# STM32F103.net
KiCad netlist of a schematic drawn in Altium Designer
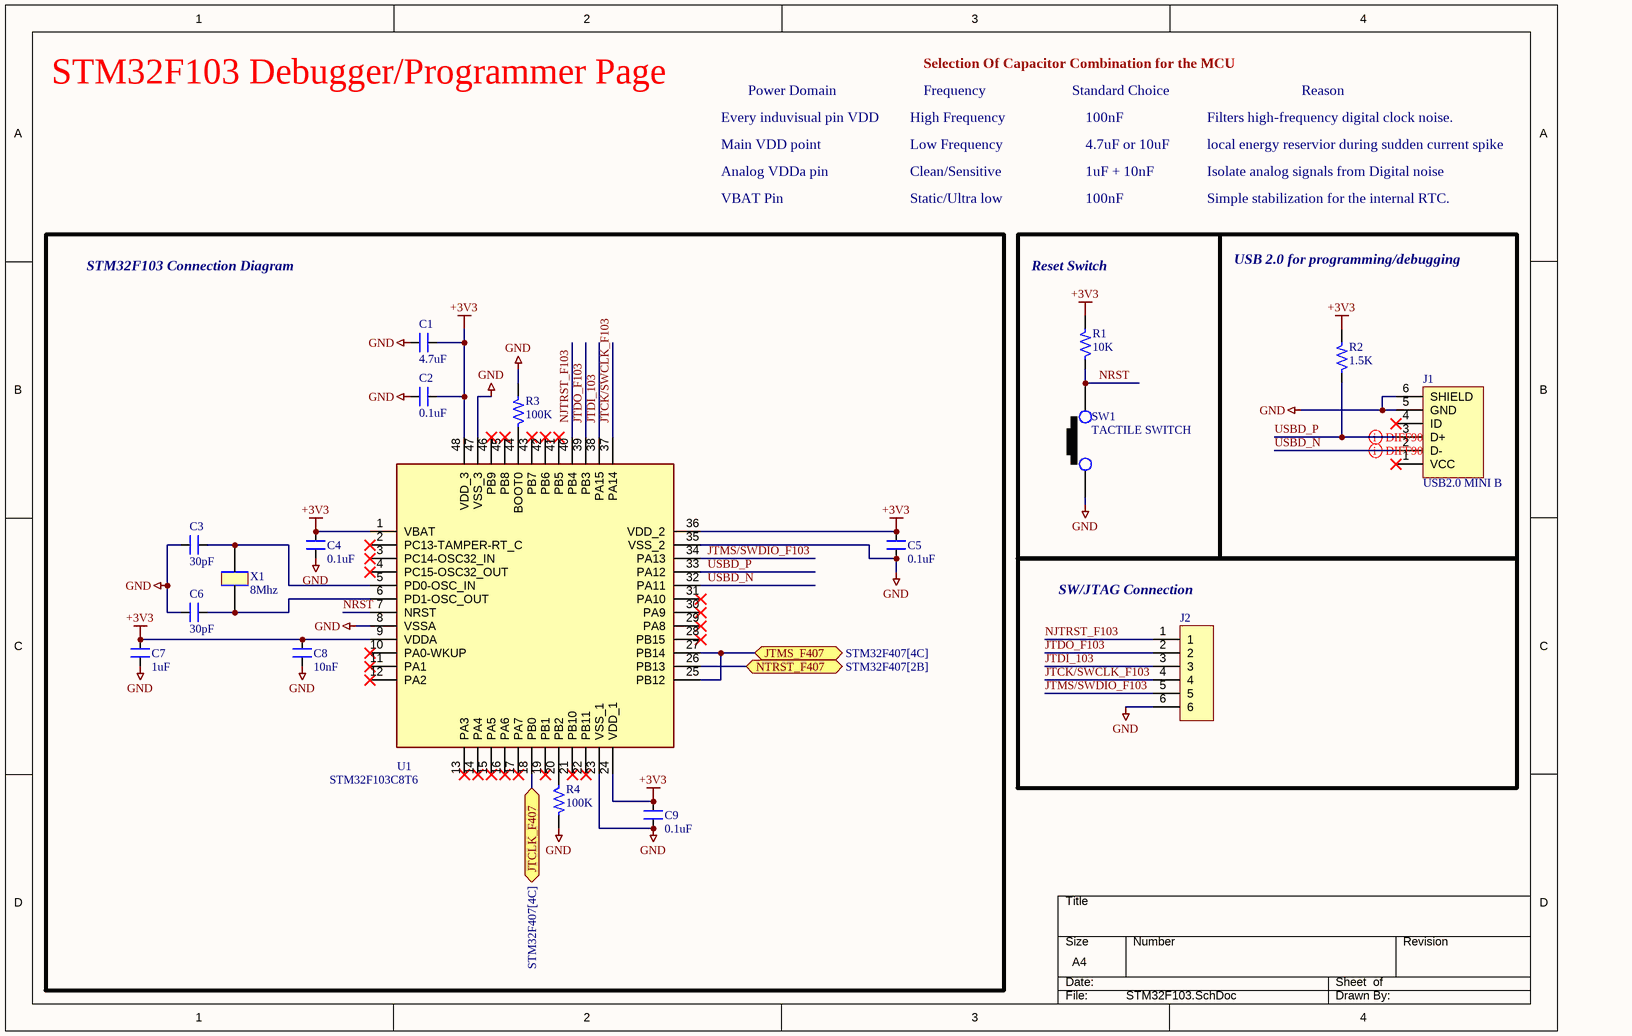
[diagram p0: STM32F103.SchDoc]

(export (version "E")
  (design (tool "Eeschema 10.0.6"))
  (components
    (comp (ref "C1")
      (value "4.7uF")
      (footprint "CAP_0805")
      (description "4.7µF ±10% 50V Ceramic Capacitor X5R 0805 (2012 Metric)")
      (fields
        (field (name "MANUFACTURER") "Yageo")
        (field (name "MANUFACTURER PART NUMBER") "GRM21BR61H475KE51L")
      )
      (libsource (lib "ESTEEMPCBLIB") (part "CAP_4.7uF-50V-10%-0805"))
    )
    (comp (ref "C2")
      (value "0.1uF")
      (footprint "CAP_0805")
      (description "0.1µF ±10% 50V Ceramic Capacitor X7R 0805 (2012 Metric)")
      (fields
        (field (name "MANUFACTURER") "Samsung")
        (field (name "MANUFACTURER PART NUMBER") "CL21B104KBCNNNC")
      )
      (libsource (lib "ESTEEMPCBLIB") (part "CAP_0.1uF-50V-10%-0805"))
    )
    (comp (ref "C3")
      (value "30pF")
      (footprint "CAP_0805")
      (description "±10% 50V Ceramic Capacitor C0G, NP0 0805 (2012 Metric)")
      (fields
        (field (name "MANUFACTURER PART NUMBER") "C0805C300K5GAC7800")
        (field (name "MANUFACTURER") "KEMET")
      )
      (libsource (lib "ESTEEMPCBLIB") (part "CAP_30pF-50V-10%-0805"))
    )
    (comp (ref "C4")
      (value "0.1uF")
      (footprint "CAP_0805")
      (description "0.1µF ±10% 50V Ceramic Capacitor X7R 0805 (2012 Metric)")
      (fields
        (field (name "MANUFACTURER") "Samsung")
        (field (name "MANUFACTURER PART NUMBER") "CL21B104KBCNNNC")
      )
      (libsource (lib "ESTEEMPCBLIB") (part "CAP_0.1uF-50V-10%-0805"))
    )
    (comp (ref "C5")
      (value "0.1uF")
      (footprint "CAP_0805")
      (description "0.1µF ±10% 50V Ceramic Capacitor X7R 0805 (2012 Metric)")
      (fields
        (field (name "MANUFACTURER") "Samsung")
        (field (name "MANUFACTURER PART NUMBER") "CL21B104KBCNNNC")
      )
      (libsource (lib "ESTEEMPCBLIB") (part "CAP_0.1uF-50V-10%-0805"))
    )
    (comp (ref "C6")
      (value "30pF")
      (footprint "CAP_0805")
      (description "±10% 50V Ceramic Capacitor C0G, NP0 0805 (2012 Metric)")
      (fields
        (field (name "MANUFACTURER PART NUMBER") "C0805C300K5GAC7800")
        (field (name "MANUFACTURER") "KEMET")
      )
      (libsource (lib "ESTEEMPCBLIB") (part "CAP_30pF-50V-10%-0805"))
    )
    (comp (ref "C7")
      (value "1uF")
      (footprint "CAP_0805")
      (description "1µF ±5% 50V Ceramic Capacitor X7R 0805 (2012 Metric)")
      (fields
        (field (name "MANUFACTURER") "Samsung")
        (field (name "MANUFACTURER PART NUMBER") "CC0805JKX7R9BB105")
      )
      (libsource (lib "ESTEEMPCBLIB") (part "CAP_1uF-50V-5%-0805"))
    )
    (comp (ref "C8")
      (value "10nF")
      (footprint "CAP_0805")
      (description "10000pF ±10% 50V Ceramic Capacitor X7R 0805 (2012 Metric)")
      (fields
        (field (name "MANUFACTURER") "Samsung")
        (field (name "MANUFACTURER PART NUMBER") "C0805C103K5RECAUTO")
      )
      (libsource (lib "ESTEEMPCBLIB") (part "CAP_10nF-50V-10%-0805"))
    )
    (comp (ref "C9")
      (value "0.1uF")
      (footprint "CAP_0805")
      (description "0.1µF ±10% 50V Ceramic Capacitor X7R 0805 (2012 Metric)")
      (fields
        (field (name "MANUFACTURER") "Samsung")
        (field (name "MANUFACTURER PART NUMBER") "CL21B104KBCNNNC")
      )
      (libsource (lib "ESTEEMPCBLIB") (part "CAP_0.1uF-50V-10%-0805"))
    )
    (comp (ref "J1")
      (value "USB2.0 MINI B")
      (footprint "CON_690-005-299-043")
      (description "USB - mini B USB 2.0 Receptacle Connector 5 Position Surface Mount, Right Angle")
      (fields
        (field (name "MANUFACTURER") "EDAC")
        (field (name "MANUFACTURER PART NUMBER") "690-005-299-043")
      )
      (libsource (lib "ESTEEMPCBLIB") (part "CON_USB2.0-MINIB-SMD"))
    )
    (comp (ref "J2")
      (value "Bergstrip 2.54mm")
      (footprint "CON6_100_59D78_TH_ST")
      (description "6 Pins, 1 Row 2.54mm Pitch, Straight bergstrip, Female")
      (fields (field (name "MANUFACTURER") "Molex") (field (name "MANUFACTURER PART NUMBER") "22-10-2061"))
      (libsource (lib "ESTEEMPCBLIB") (part "CON-BS-SKT_6X1-100-ST-TH"))
    )
    (comp (ref "R1")
      (value "10K")
      (footprint "RES_0805")
      (description "10 kOhms ±1% 0.125W, 1/8W Chip Resistor 0805 (2012 Metric) Automotive AEC-Q200 Thick Film")
      (fields (field (name "MANUFACTURER") "CTS") (field (name "MANUFACTURER PART NUMBER") "WR08X1002FTL"))
      (libsource (lib "ESTEEMPCBLIB") (part "RES_10K-0.125W-1%-0805"))
    )
    (comp (ref "R2")
      (value "1.5K")
      (footprint "RES_0805")
      (description "1.5 kOhms ±1% 0.125W, 1/8W Chip Resistor 0805 (2012 Metric) Thick Film")
      (fields
        (field (name "MANUFACTURER") "TE Connectivity Passive Product")
        (field (name "MANUFACTURER PART NUMBER") "CRG0805F1K5")
      )
      (libsource (lib "ESTEEMPCBLIB") (part "RES_1.5K-0.125W-1%-0805"))
    )
    (comp (ref "R3")
      (value "100K")
      (footprint "RES_0603")
      (description "100 kOhms ±1% 0.1W, 1/10W Chip Resistor 0603 (1608 Metric) Automotive AEC-Q200 Thick Film")
      (fields
        (field (name "MANUFACTURER") "Stackpole Electronics")
        (field (name "MANUFACTURER PART NUMBER") "RMCF0603FT100K")
      )
      (libsource (lib "ESTEEMPCBLIB") (part "RES_100K-0.1W-1%-0603"))
    )
    (comp (ref "R4")
      (value "100K")
      (footprint "RES_0603")
      (description "100 kOhms ±1% 0.1W, 1/10W Chip Resistor 0603 (1608 Metric) Automotive AEC-Q200 Thick Film")
      (fields
        (field (name "MANUFACTURER") "Stackpole Electronics")
        (field (name "MANUFACTURER PART NUMBER") "RMCF0603FT100K")
      )
      (libsource (lib "ESTEEMPCBLIB") (part "RES_100K-0.1W-1%-0603"))
    )
    (comp (ref "SW1")
      (value "TACTILE SWITCH")
      (footprint "SW_342_SMD")
      (description "Tactile Switch SPST-NO Top Actuated Surface Mount")
      (fields
        (field (name "MANUFACTURER") "ITT C&K")
        (field (name "MANUFACTURER PART NUMBER") "RS-282G05A3-SMRT")
      )
      (libsource (lib "ESTEEMPCBLIB") (part "SW1_RS-282G05A3-SMRT-SMD"))
    )
    (comp (ref "U1")
      (value "STM32F103C8T6")
      (footprint "LQFP-48_19.6_393_58X11_SMD")
      (description "ARM® Cortex®-M3 STM32F1 Microcontroller IC 32-Bit 72MHz 64KB (64K x 8) FLASH 48-LQFP (7x7)")
      (fields (field (name "MANUFACTURER") "STMicroelectronics"))
      (libsource (lib "ESTEEMPCBLIB") (part "IC_STM32F103C8T6"))
    )
    (comp (ref "X1")
      (value "8Mhz")
      (footprint "XTAL_314_240X47_SMD")
      (description "8MHz ±30ppm Crystal 32pF 60 Ohms HC-49/US")
      (fields
        (field (name "MANUFACTURER") "Fox Electronics")
        (field (name "MANUFACTURER PART NUMBER") "ECS-80-32-5PX-TR")
      )
      (libsource (lib "ESTEEMPCBLIB") (part "XTAL_8MHZ-ECS-80-32-5PX-SMD"))
    )
  )
  (nets
    (net (code "1") (name "+3V3") (class "Default")
      (node (ref "C1") (pin "2") (pinfunction "2_2") (pintype "passive"))
      (node (ref "C2") (pin "2") (pinfunction "2_2") (pintype "passive"))
      (node (ref "C4") (pin "2") (pinfunction "2_2") (pintype "passive"))
      (node (ref "C5") (pin "2") (pinfunction "2_2") (pintype "passive"))
      (node (ref "C7") (pin "2") (pinfunction "2_2") (pintype "passive"))
      (node (ref "C8") (pin "2") (pinfunction "2_2") (pintype "passive"))
      (node (ref "C9") (pin "2") (pinfunction "2_2") (pintype "passive"))
      (node (ref "R1") (pin "2") (pinfunction "2_2") (pintype "passive"))
      (node (ref "R2") (pin "2") (pinfunction "2_2") (pintype "passive"))
      (node (ref "U1") (pin "1") (pinfunction "VBAT_1") (pintype "passive"))
      (node (ref "U1") (pin "24") (pinfunction "VDD_1_24") (pintype "passive"))
      (node (ref "U1") (pin "36") (pinfunction "VDD_2_36") (pintype "passive"))
      (node (ref "U1") (pin "48") (pinfunction "VDD_3_48") (pintype "passive"))
      (node (ref "U1") (pin "9") (pinfunction "VDDA_9") (pintype "passive"))
    )
    (net (code "2") (name "/JTCK{slash}SWCLK_F103") (class "Default")
      (node (ref "J2") (pin "4") (pinfunction "4_4") (pintype "passive"))
      (node (ref "U1") (pin "37") (pinfunction "PA14_37") (pintype "passive"))
    )
    (net (code "3") (name "/JTCLK_F407") (class "Default")
      (node (ref "U1") (pin "18") (pinfunction "PB0_18") (pintype "passive"))
    )
    (net (code "4") (name "/JTDI_103") (class "Default")
      (node (ref "J2") (pin "3") (pinfunction "3_3") (pintype "passive"))
      (node (ref "U1") (pin "38") (pinfunction "PA15_38") (pintype "passive"))
    )
    (net (code "5") (name "/JTDO_F103") (class "Default")
      (node (ref "J2") (pin "2") (pinfunction "2_2") (pintype "passive"))
      (node (ref "U1") (pin "39") (pinfunction "PB3_39") (pintype "passive"))
    )
    (net (code "6") (name "/JTMS_F407") (class "Default")
      (node (ref "U1") (pin "25") (pinfunction "PB12_25") (pintype "passive"))
      (node (ref "U1") (pin "27") (pinfunction "PB14_27") (pintype "passive"))
    )
    (net (code "7") (name "/JTMS{slash}SWDIO_F103") (class "Default")
      (node (ref "J2") (pin "5") (pinfunction "5_5") (pintype "passive"))
      (node (ref "U1") (pin "34") (pinfunction "PA13_34") (pintype "passive"))
    )
    (net (code "8") (name "/NJTRST_F103") (class "Default")
      (node (ref "J2") (pin "1") (pinfunction "1_1") (pintype "passive"))
      (node (ref "U1") (pin "40") (pinfunction "PB4_40") (pintype "passive"))
    )
    (net (code "9") (name "/NRST") (class "Default")
      (node (ref "R1") (pin "1") (pinfunction "1_1") (pintype "passive"))
      (node (ref "SW1") (pin "2") (pinfunction "2_2") (pintype "passive"))
      (node (ref "U1") (pin "7") (pinfunction "NRST_7") (pintype "passive"))
    )
    (net (code "10") (name "/NTRST_F407") (class "Default")
      (node (ref "U1") (pin "26") (pinfunction "PB13_26") (pintype "passive"))
    )
    (net (code "11") (name "/USBD_N") (class "Default")
      (node (ref "J1") (pin "2") (pinfunction "D-_2") (pintype "passive"))
      (node (ref "U1") (pin "32") (pinfunction "PA11_32") (pintype "passive"))
    )
    (net (code "12") (name "/USBD_P") (class "Default")
      (node (ref "J1") (pin "3") (pinfunction "D+_3") (pintype "passive"))
      (node (ref "R2") (pin "1") (pinfunction "1_1") (pintype "passive"))
      (node (ref "U1") (pin "33") (pinfunction "PA12_33") (pintype "passive"))
    )
    (net (code "13") (name "GND") (class "Default")
      (node (ref "C1") (pin "1") (pinfunction "1_1") (pintype "passive"))
      (node (ref "C2") (pin "1") (pinfunction "1_1") (pintype "passive"))
      (node (ref "C3") (pin "2") (pinfunction "2_2") (pintype "passive"))
      (node (ref "C4") (pin "1") (pinfunction "1_1") (pintype "passive"))
      (node (ref "C5") (pin "1") (pinfunction "1_1") (pintype "passive"))
      (node (ref "C6") (pin "2") (pinfunction "2_2") (pintype "passive"))
      (node (ref "C7") (pin "1") (pinfunction "1_1") (pintype "passive"))
      (node (ref "C8") (pin "1") (pinfunction "1_1") (pintype "passive"))
      (node (ref "C9") (pin "1") (pinfunction "1_1") (pintype "passive"))
      (node (ref "J1") (pin "5") (pinfunction "GND_5") (pintype "passive"))
      (node (ref "J1") (pin "6") (pinfunction "SHIELD_6") (pintype "passive"))
      (node (ref "J2") (pin "6") (pinfunction "6_6") (pintype "passive"))
      (node (ref "R3") (pin "2") (pinfunction "2_2") (pintype "passive"))
      (node (ref "R4") (pin "2") (pinfunction "2_2") (pintype "passive"))
      (node (ref "SW1") (pin "1") (pinfunction "1_1") (pintype "passive"))
      (node (ref "U1") (pin "23") (pinfunction "VSS_1_23") (pintype "passive"))
      (node (ref "U1") (pin "35") (pinfunction "VSS_2_35") (pintype "passive"))
      (node (ref "U1") (pin "47") (pinfunction "VSS_3_47") (pintype "passive"))
      (node (ref "U1") (pin "8") (pinfunction "VSSA_8") (pintype "passive"))
    )
    (net (code "14") (name "Net-(U1-BOOT0)") (class "Default")
      (node (ref "R3") (pin "1") (pinfunction "1_1") (pintype "passive"))
      (node (ref "U1") (pin "44") (pinfunction "BOOT0_44") (pintype "passive"))
    )
    (net (code "15") (name "Net-(U1-PB2)") (class "Default")
      (node (ref "R4") (pin "1") (pinfunction "1_1") (pintype "passive"))
      (node (ref "U1") (pin "20") (pinfunction "PB2_20") (pintype "passive"))
    )
    (net (code "16") (name "Net-(U1-PD0-OSC_IN)") (class "Default")
      (node (ref "C3") (pin "1") (pinfunction "1_1") (pintype "passive"))
      (node (ref "U1") (pin "5") (pinfunction "PD0-OSC_IN_5") (pintype "passive"))
      (node (ref "X1") (pin "2") (pinfunction "2_2") (pintype "passive"))
    )
    (net (code "17") (name "Net-(U1-PD1-OSC_OUT)") (class "Default")
      (node (ref "C6") (pin "1") (pinfunction "1_1") (pintype "passive"))
      (node (ref "U1") (pin "6") (pinfunction "PD1-OSC_OUT_6") (pintype "passive"))
      (node (ref "X1") (pin "1") (pinfunction "1_1") (pintype "passive"))
    )
    (net (code "18") (name "unconnected-(J1-ID-Pad4)") (class "Default")
      (node (ref "J1") (pin "4") (pinfunction "ID_4") (pintype "passive+no_connect"))
    )
    (net (code "19") (name "unconnected-(J1-VCC-Pad1)") (class "Default")
      (node (ref "J1") (pin "1") (pinfunction "VCC_1") (pintype "passive+no_connect"))
    )
    (net (code "20") (name "unconnected-(U1-PA0-WKUP-Pad10)") (class "Default")
      (node (ref "U1") (pin "10") (pinfunction "PA0-WKUP_10") (pintype "passive+no_connect"))
    )
    (net (code "21") (name "unconnected-(U1-PA1-Pad11)") (class "Default")
      (node (ref "U1") (pin "11") (pinfunction "PA1_11") (pintype "passive+no_connect"))
    )
    (net (code "22") (name "unconnected-(U1-PA2-Pad12)") (class "Default")
      (node (ref "U1") (pin "12") (pinfunction "PA2_12") (pintype "passive+no_connect"))
    )
    (net (code "23") (name "unconnected-(U1-PA3-Pad13)") (class "Default")
      (node (ref "U1") (pin "13") (pinfunction "PA3_13") (pintype "passive+no_connect"))
    )
    (net (code "24") (name "unconnected-(U1-PA4-Pad14)") (class "Default")
      (node (ref "U1") (pin "14") (pinfunction "PA4_14") (pintype "passive+no_connect"))
    )
    (net (code "25") (name "unconnected-(U1-PA5-Pad15)") (class "Default")
      (node (ref "U1") (pin "15") (pinfunction "PA5_15") (pintype "passive+no_connect"))
    )
    (net (code "26") (name "unconnected-(U1-PA6-Pad16)") (class "Default")
      (node (ref "U1") (pin "16") (pinfunction "PA6_16") (pintype "passive+no_connect"))
    )
    (net (code "27") (name "unconnected-(U1-PA7-Pad17)") (class "Default")
      (node (ref "U1") (pin "17") (pinfunction "PA7_17") (pintype "passive+no_connect"))
    )
    (net (code "28") (name "unconnected-(U1-PA8-Pad29)") (class "Default")
      (node (ref "U1") (pin "29") (pinfunction "PA8_29") (pintype "passive+no_connect"))
    )
    (net (code "29") (name "unconnected-(U1-PA9-Pad30)") (class "Default")
      (node (ref "U1") (pin "30") (pinfunction "PA9_30") (pintype "passive+no_connect"))
    )
    (net (code "30") (name "unconnected-(U1-PA10-Pad31)") (class "Default")
      (node (ref "U1") (pin "31") (pinfunction "PA10_31") (pintype "passive+no_connect"))
    )
    (net (code "31") (name "unconnected-(U1-PB1-Pad19)") (class "Default")
      (node (ref "U1") (pin "19") (pinfunction "PB1_19") (pintype "passive+no_connect"))
    )
    (net (code "32") (name "unconnected-(U1-PB5-Pad41)") (class "Default")
      (node (ref "U1") (pin "41") (pinfunction "PB5_41") (pintype "passive+no_connect"))
    )
    (net (code "33") (name "unconnected-(U1-PB6-Pad42)") (class "Default")
      (node (ref "U1") (pin "42") (pinfunction "PB6_42") (pintype "passive+no_connect"))
    )
    (net (code "34") (name "unconnected-(U1-PB7-Pad43)") (class "Default")
      (node (ref "U1") (pin "43") (pinfunction "PB7_43") (pintype "passive+no_connect"))
    )
    (net (code "35") (name "unconnected-(U1-PB8-Pad45)") (class "Default")
      (node (ref "U1") (pin "45") (pinfunction "PB8_45") (pintype "passive+no_connect"))
    )
    (net (code "36") (name "unconnected-(U1-PB9-Pad46)") (class "Default")
      (node (ref "U1") (pin "46") (pinfunction "PB9_46") (pintype "passive+no_connect"))
    )
    (net (code "37") (name "unconnected-(U1-PB10-Pad21)") (class "Default")
      (node (ref "U1") (pin "21") (pinfunction "PB10_21") (pintype "passive+no_connect"))
    )
    (net (code "38") (name "unconnected-(U1-PB11-Pad22)") (class "Default")
      (node (ref "U1") (pin "22") (pinfunction "PB11_22") (pintype "passive+no_connect"))
    )
    (net (code "39") (name "unconnected-(U1-PB15-Pad28)") (class "Default")
      (node (ref "U1") (pin "28") (pinfunction "PB15_28") (pintype "passive+no_connect"))
    )
    (net (code "40") (name "unconnected-(U1-PC13-TAMPER-RT_C-Pad2)") (class "Default")
      (node (ref "U1") (pin "2") (pinfunction "PC13-TAMPER-RT_C_2") (pintype "passive+no_connect"))
    )
    (net (code "41") (name "unconnected-(U1-PC14-OSC32_IN-Pad3)") (class "Default")
      (node (ref "U1") (pin "3") (pinfunction "PC14-OSC32_IN_3") (pintype "passive+no_connect"))
    )
    (net (code "42") (name "unconnected-(U1-PC15-OSC32_OUT-Pad4)") (class "Default")
      (node (ref "U1") (pin "4") (pinfunction "PC15-OSC32_OUT_4") (pintype "passive+no_connect"))
    )
  )
)
